# CH32V467VET-USB.net
KiCad netlist of a schematic drawn in Altium Designer
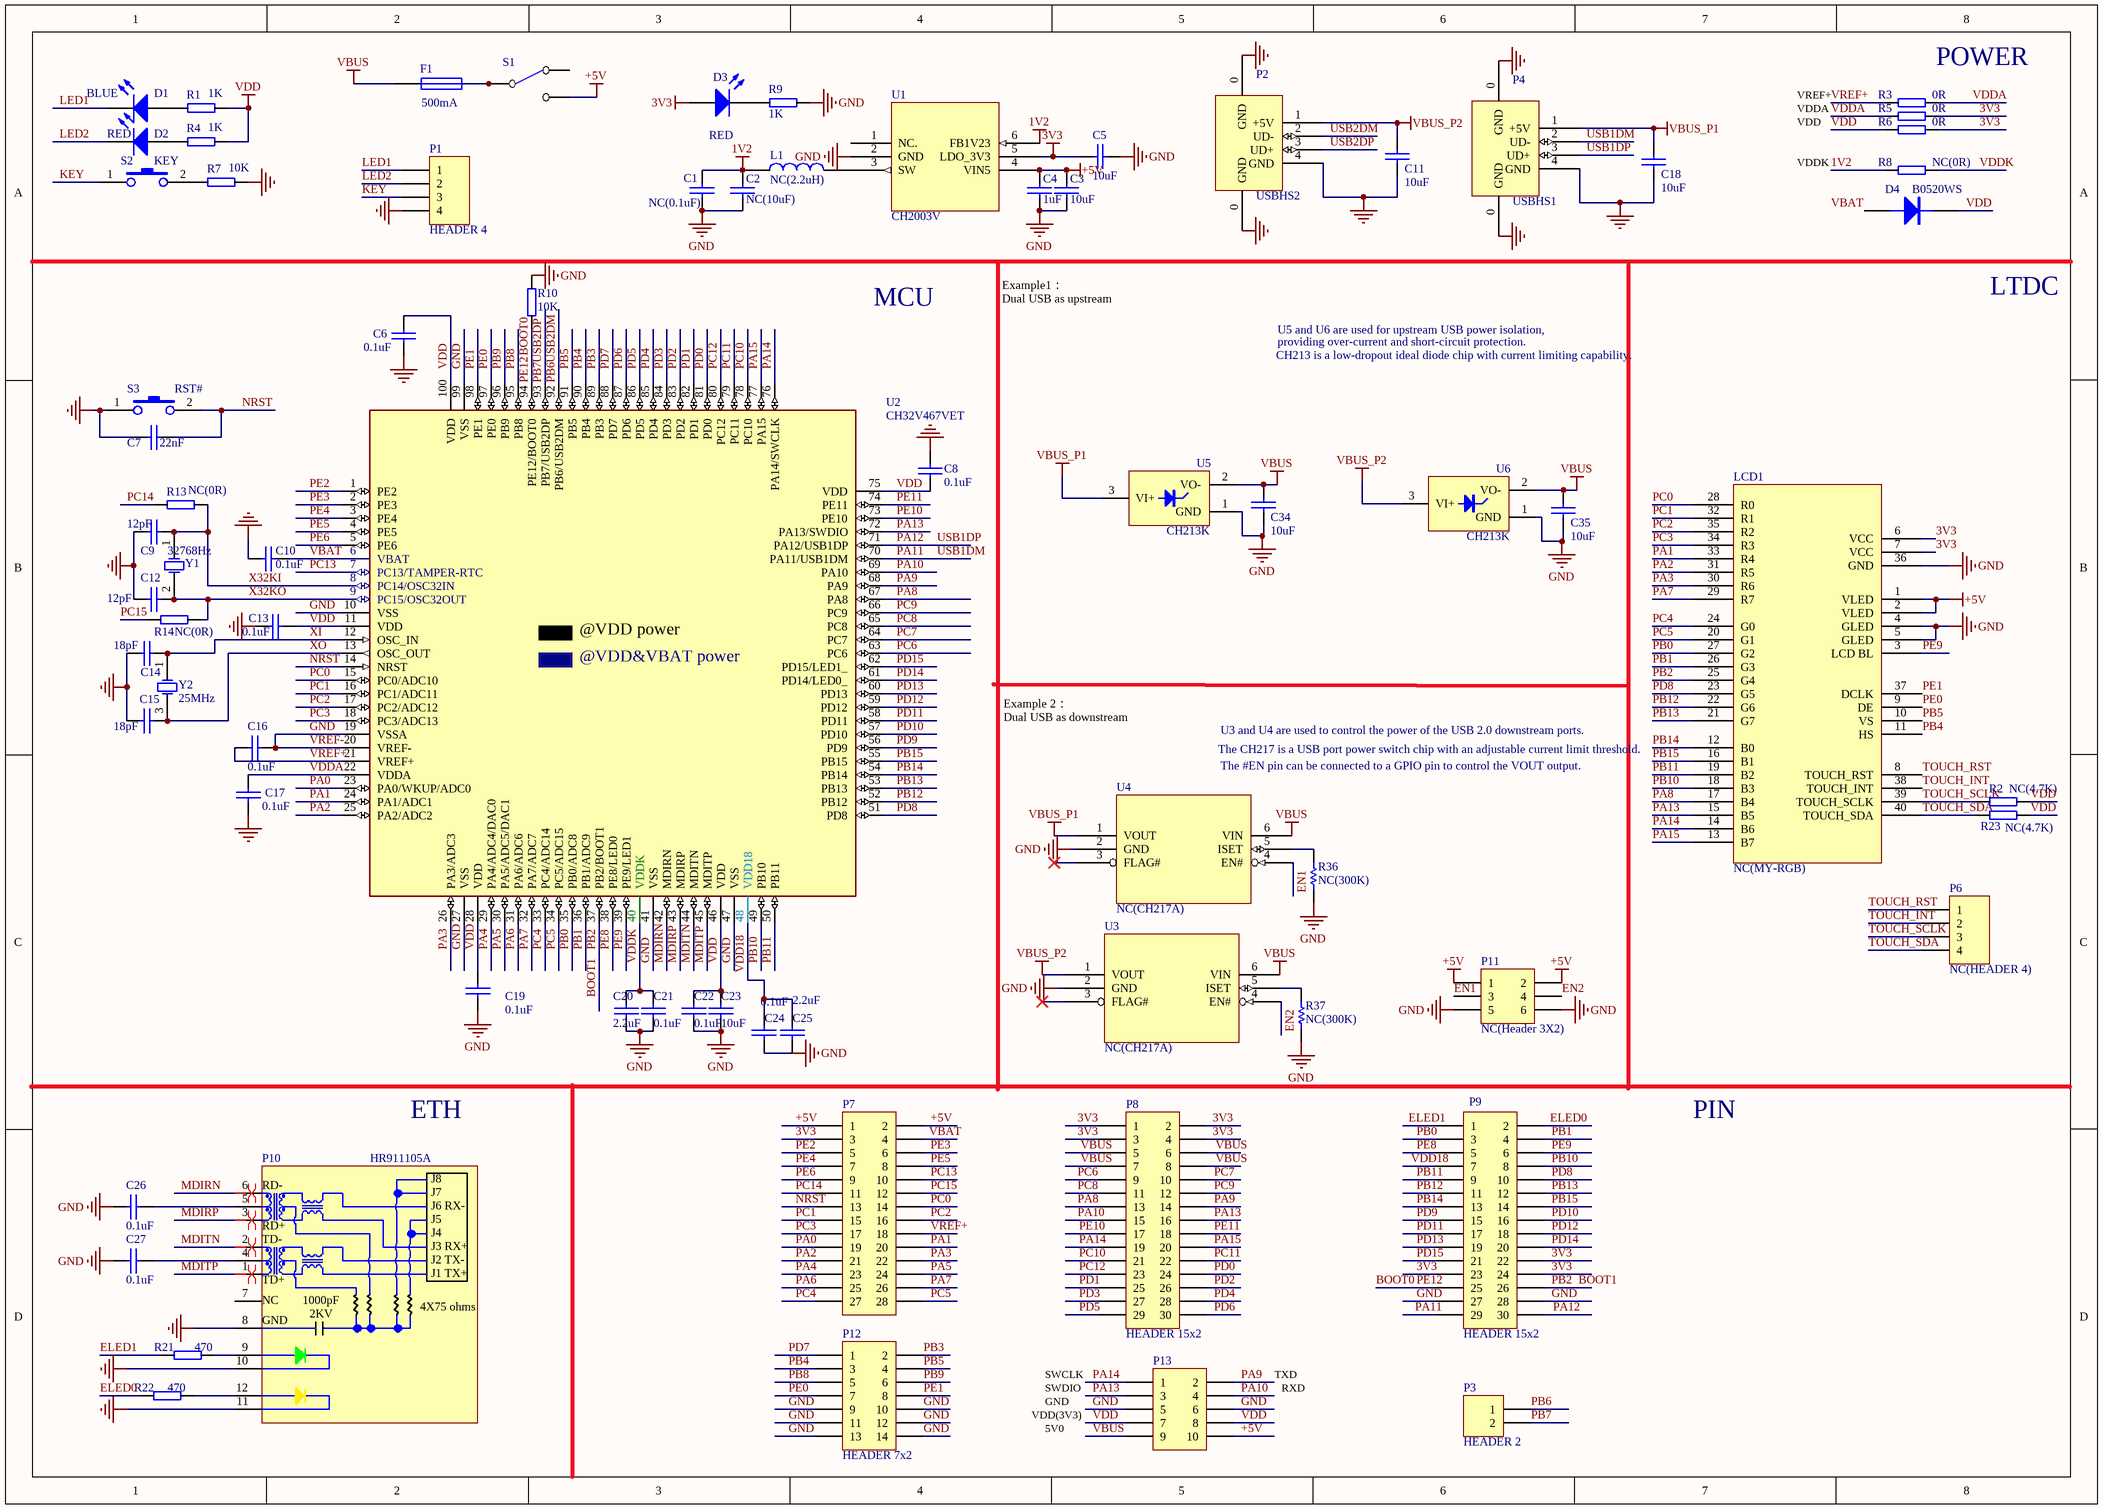
[diagram p0: CH32V467VET-USB.SchDoc]

(export (version "E")
  (design (tool "Eeschema 10.0.6"))
  (components
    (comp (ref "C1")
      (value "NC(0.1uF)")
      (footprint "0402_C")
      (description "Capacitor")
      (libsource (lib "") (part "CAP_2"))
    )
    (comp (ref "C2")
      (value "NC(10uF)")
      (footprint "0603_C")
      (description "Capacitor")
      (libsource (lib "*") (part "CAP"))
    )
    (comp (ref "C3")
      (value "10uF")
      (footprint "0603_C")
      (description "Capacitor")
      (libsource (lib "*") (part "CAP"))
    )
    (comp (ref "C4")
      (value "1uF")
      (footprint "0402_C")
      (description "Capacitor")
      (libsource (lib "") (part "CAP_2"))
    )
    (comp (ref "C5")
      (value "10uF")
      (footprint "0603_C")
      (description "Capacitor")
      (libsource (lib "*") (part "CAP"))
    )
    (comp (ref "C6")
      (value "0.1uF")
      (footprint "0402_C")
      (description "Capacitor")
      (libsource (lib "*") (part "CAP"))
    )
    (comp (ref "C7")
      (value "22nF")
      (footprint "0402_C")
      (description "Capacitor")
      (libsource (lib "") (part "CAP_1"))
    )
    (comp (ref "C8")
      (value "0.1uF")
      (footprint "0402_C")
      (description "Capacitor")
      (libsource (lib "*") (part "CAP"))
    )
    (comp (ref "C9")
      (value "12pF")
      (footprint "0402_C")
      (description "Capacitor")
      (libsource (lib "*") (part "CAP"))
    )
    (comp (ref "C10")
      (value "0.1uF")
      (footprint "0402_C")
      (description "Capacitor")
      (libsource (lib "*") (part "CAP"))
    )
    (comp (ref "C11")
      (value "10uF")
      (footprint "0603_C")
      (description "Capacitor")
      (libsource (lib "") (part "CAP_1"))
    )
    (comp (ref "C12")
      (value "12pF")
      (footprint "0402_C")
      (description "Capacitor")
      (libsource (lib "*") (part "CAP"))
    )
    (comp (ref "C13")
      (value "0.1uF")
      (footprint "0402_C")
      (description "Capacitor")
      (libsource (lib "*") (part "CAP"))
    )
    (comp (ref "C14")
      (value "18pF")
      (footprint "0402_C")
      (description "Capacitor")
      (libsource (lib "*") (part "CAP"))
    )
    (comp (ref "C15")
      (value "18pF")
      (footprint "0402_C")
      (description "Capacitor")
      (libsource (lib "*") (part "CAP"))
    )
    (comp (ref "C16")
      (value "0.1uF")
      (footprint "0402_C")
      (description "Capacitor")
      (libsource (lib "*") (part "CAP"))
    )
    (comp (ref "C17")
      (value "0.1uF")
      (footprint "0402_C")
      (description "Capacitor")
      (libsource (lib "*") (part "CAP"))
    )
    (comp (ref "C18")
      (value "10uF")
      (footprint "0603_C")
      (description "Capacitor")
      (libsource (lib "") (part "CAP_1"))
    )
    (comp (ref "C19")
      (value "0.1uF")
      (footprint "0402_C")
      (description "Capacitor")
      (libsource (lib "*") (part "CAP"))
    )
    (comp (ref "C20")
      (value "2.2uF")
      (footprint "0402_C")
      (description "Capacitor")
      (libsource (lib "*") (part "CAP"))
    )
    (comp (ref "C21")
      (value "0.1uF")
      (footprint "0402_C")
      (description "Capacitor")
      (libsource (lib "*") (part "CAP"))
    )
    (comp (ref "C22")
      (value "0.1uF")
      (footprint "0402_C")
      (description "Capacitor")
      (libsource (lib "*") (part "CAP"))
    )
    (comp (ref "C23")
      (value "10uF")
      (footprint "0402_C")
      (description "Capacitor")
      (libsource (lib "*") (part "CAP"))
    )
    (comp (ref "C24")
      (value "0.1uF")
      (footprint "0402_C")
      (description "Capacitor")
      (libsource (lib "*") (part "CAP"))
    )
    (comp (ref "C25")
      (value "2.2uF")
      (footprint "0402_C")
      (description "Capacitor")
      (libsource (lib "*") (part "CAP"))
    )
    (comp (ref "C26")
      (value "0.1uF")
      (footprint "0402_C")
      (description "Capacitor")
      (libsource (lib "wch_sch_others") (part "CAP"))
    )
    (comp (ref "C27")
      (value "0.1uF")
      (footprint "0402_C")
      (description "Capacitor")
      (libsource (lib "wch_sch_others") (part "CAP"))
    )
    (comp (ref "C34")
      (value "10uF")
      (footprint "0603_C")
      (description "Capacitor")
      (libsource (lib "") (part "CAP_1"))
    )
    (comp (ref "C35")
      (value "10uF")
      (footprint "0603_C")
      (description "Capacitor")
      (libsource (lib "") (part "CAP_1"))
    )
    (comp (ref "D1")
      (value "BLUE")
      (footprint "0603+")
      (description "Typical INFRARED GaAs LED")
      (fields (field (name "PUBLISHER") "Altium Limited"))
      (libsource (lib "*") (part "LED0"))
    )
    (comp (ref "D2")
      (value "RED")
      (footprint "0603+")
      (description "Typical INFRARED GaAs LED")
      (fields (field (name "PUBLISHER") "Altium Limited"))
      (libsource (lib "*") (part "LED0"))
    )
    (comp (ref "D3")
      (value "RED")
      (footprint "0603+")
      (description "Typical INFRARED GaAs LED")
      (fields (field (name "PUBLISHER") "Altium Limited"))
      (libsource (lib "*") (part "LED0"))
    )
    (comp (ref "D4")
      (value "B0520WS")
      (footprint "SOD-323")
      (description "Diode")
      (libsource (lib "*") (part "DIODE"))
    )
    (comp (ref "F1")
      (value "500mA")
      (footprint "0603")
      (description "Fuse")
      (libsource (lib "wch_sch_others") (part "FUSE1"))
    )
    (comp (ref "L1") (value "NC(2.2uH)") (footprint "CD32") (libsource (lib "*") (part "INDUCTOR")))
    (comp (ref "LCD1")
      (value "NC(MY-RGB)")
      (footprint "FPC40P-0.5-FK750M3")
      (libsource (lib "MY-显示") (part "MY-RGB"))
    )
    (comp (ref "P1")
      (value "HEADER 4")
      (footprint "SIP4-2.54mm")
      (description "Header, 4-Pin")
      (libsource (lib "wch_sch_others") (part "HEADER 4"))
    )
    (comp (ref "P2")
      (value "USBHS2")
      (footprint "USBAF")
      (description "USB Port")
      (libsource (lib "*") (part "USB"))
    )
    (comp (ref "P3")
      (value "HEADER 2")
      (footprint "MYPCB:SIP2-2.54mm")
      (description "Header, 2-Pin")
      (libsource (lib "wch_sch_others") (part "HEADER 2"))
    )
    (comp (ref "P4")
      (value "USBHS1")
      (footprint "USBAF")
      (description "USB Port")
      (libsource (lib "*") (part "USB"))
    )
    (comp (ref "P6")
      (value "NC(HEADER 4)")
      (footprint "SIP4-2.54mm")
      (description "Header, 4-Pin")
      (libsource (lib "wch_sch_others") (part "HEADER 4"))
    )
    (comp (ref "P7")
      (value "HEADER 14x2")
      (footprint "MYPCB:IDC28-2.54MM")
      (description "Header, 14-Pin, Dual row")
      (libsource (lib "wch_sch_others") (part "HEADER 14x2"))
    )
    (comp (ref "P8")
      (value "HEADER 15x2")
      (footprint "MYPCB:IDC30-2.54MM")
      (description "Header, 15-Pin, Dual row")
      (libsource (lib "wch_sch_others") (part "HEADER 15x2"))
    )
    (comp (ref "P9")
      (value "HEADER 15x2")
      (footprint "MYPCB:IDC30-2.54MM")
      (description "Header, 15-Pin, Dual row")
      (libsource (lib "wch_sch_others") (part "HEADER 15x2"))
    )
    (comp (ref "P10") (value "HR911105A") (footprint "HR911105A") (libsource (lib "*") (part "HR911105A")))
    (comp (ref "P11")
      (value "NC(Header 3X2)")
      (footprint "HDR2X3")
      (description "Header, 3-Pin, Dual row")
      (fields (field (name "PUBLISHER") "Altium Limited"))
      (libsource (lib "Miscellaneous Connectors") (part "Header 3X2"))
    )
    (comp (ref "P12")
      (value "HEADER 7x2")
      (footprint "MYPCB:IDC14-2.54mm")
      (description "Header, 7-Pin, Dual row")
      (libsource (lib "wch_sch_others") (part "HEADER 7x2"))
    )
    (comp (ref "P13")
      (value "LINK")
      (footprint "IDC10-2.54mm")
      (description "Header, 5-Pin, Dual row, Right Angle")
      (fields (field (name "PUBLISHER") "Altium Limited"))
      (libsource (lib "Miscellaneous Connectors") (part "Header 5X2H"))
    )
    (comp (ref "R1") (value "1K") (footprint "0402") (libsource (lib "wch_sch_others") (part "RES")))
    (comp (ref "R2") (value "NC(4.7K)") (footprint "0402") (libsource (lib "wch_sch_others") (part "RES")))
    (comp (ref "R3") (value "0R") (footprint "0402") (libsource (lib "*") (part "R")))
    (comp (ref "R4") (value "1K") (footprint "0402") (libsource (lib "wch_sch_others") (part "RES")))
    (comp (ref "R5") (value "0R") (footprint "0402") (libsource (lib "*") (part "R")))
    (comp (ref "R6") (value "0R") (footprint "0402") (libsource (lib "*") (part "R")))
    (comp (ref "R7") (value "10K") (footprint "0402") (libsource (lib "wch_sch_others") (part "RES")))
    (comp (ref "R8") (value "NC(0R)") (footprint "0402") (libsource (lib "*") (part "R")))
    (comp (ref "R9") (value "1K") (footprint "0402") (libsource (lib "wch_sch_others") (part "RES")))
    (comp (ref "R10") (value "10K") (footprint "0402") (libsource (lib "wch_sch_others") (part "RES")))
    (comp (ref "R13") (value "NC(0R)") (footprint "0402") (libsource (lib "wch_sch_others") (part "RES")))
    (comp (ref "R14") (value "NC(0R)") (footprint "0402") (libsource (lib "wch_sch_others") (part "RES")))
    (comp (ref "R21") (value "470") (footprint "0402") (libsource (lib "wch_sch_others") (part "RES")))
    (comp (ref "R22") (value "470") (footprint "0402") (libsource (lib "wch_sch_others") (part "RES")))
    (comp (ref "R23") (value "NC(4.7K)") (footprint "0402") (libsource (lib "wch_sch_others") (part "RES")))
    (comp (ref "R36")
      (value "NC(300K)")
      (footprint "0603")
      (description "Resistor")
      (fields (field (name "PUBLISHER") "Altium Limited"))
      (libsource (lib "MYLIB") (part "0603-1"))
    )
    (comp (ref "R37")
      (value "NC(300K)")
      (footprint "0603")
      (description "Resistor")
      (fields (field (name "PUBLISHER") "Altium Limited"))
      (libsource (lib "MYLIB") (part "0603-1"))
    )
    (comp (ref "S1") (value "SW SPDT") (footprint "SW1") (libsource (lib "*") (part "SW SPDT")))
    (comp (ref "S2")
      (value "KEY")
      (footprint "SMD_6.1x3.65x2.5mm-KEY")
      (libsource (lib "wch_sch_others") (part "KEY1"))
    )
    (comp (ref "S3")
      (value "RST#")
      (footprint "SMD_6.1x3.65x2.5mm-KEY")
      (libsource (lib "wch_sch_others") (part "KEY1"))
    )
    (comp (ref "U1")
      (value "CH2003V")
      (footprint "SOT-23-6")
      (description "Step-Down DC-DC Converter, 5V input, 1.23V * 800mA output, with LDO 3.3V * 200mA")
      (libsource (lib "CHXXX") (part "CH2003V"))
    )
    (comp (ref "U2")
      (value "CH32V467VET")
      (footprint "LQFP100")
      (description "RISC-V FPU HD-MCU, 175MHz, USB_480M, 100M Ethernet & Phy, CAN, DVP, ADC, DAC, SRAM")
      (libsource (lib "CHXXX") (part "CH32V467VET"))
    )
    (comp (ref "U3")
      (value "NC(CH217A)")
      (footprint "SOT-23-6")
      (description "Current-Limited USB Power Distribution Switch")
      (libsource (lib "CHXXX") (part "CH217K"))
    )
    (comp (ref "U4")
      (value "NC(CH217A)")
      (footprint "SOT-23-6")
      (description "Current-Limited USB Power Distribution Switch")
      (libsource (lib "CHXXX") (part "CH217K"))
    )
    (comp (ref "U5")
      (value "CH213K")
      (footprint "SOT-23-3")
      (description "Ideal Diode 5V*1A")
      (libsource (lib "*") (part "CH213K"))
    )
    (comp (ref "U6")
      (value "CH213K")
      (footprint "SOT-23-3")
      (description "Ideal Diode 5V*1A")
      (libsource (lib "*") (part "CH213K"))
    )
    (comp (ref "Y1")
      (value "32768Hz")
      (footprint "FC-135")
      (description "Crystal Oscillator")
      (fields (field (name "PUBLISHER") "Altium Limited"))
      (libsource (lib "") (part "XTAL_1"))
    )
    (comp (ref "Y2")
      (value "25MHz")
      (footprint "XT3225")
      (description "Crystal Oscillator")
      (fields (field (name "PUBLISHER") "Altium Limited"))
      (libsource (lib "*") (part "XTAL"))
    )
  )
  (nets
    (net (code "1") (name "+5V") (class "Default")
      (node (ref "C3") (pin "2") (pinfunction "2_2") (pintype "passive"))
      (node (ref "C4") (pin "2") (pinfunction "2_2") (pintype "passive"))
      (node (ref "LCD1") (pin "1") (pinfunction "VLED_1") (pintype "passive"))
      (node (ref "LCD1") (pin "2") (pinfunction "VLED_2") (pintype "passive"))
      (node (ref "P11") (pin "1") (pinfunction "1_1") (pintype "passive"))
      (node (ref "P11") (pin "2") (pinfunction "2_2") (pintype "passive"))
      (node (ref "P13") (pin "10") (pinfunction "10_10") (pintype "passive"))
      (node (ref "P7") (pin "1") (pinfunction "1_1") (pintype "passive"))
      (node (ref "P7") (pin "2") (pinfunction "2_2") (pintype "passive"))
      (node (ref "S1") (pin "2") (pinfunction "NC_2") (pintype "passive"))
      (node (ref "U1") (pin "4") (pinfunction "VIN5_4") (pintype "power_in"))
    )
    (net (code "3") (name "/BOOT0") (class "Default")
      (node (ref "P9") (pin "25") (pinfunction "25_25") (pintype "passive"))
      (node (ref "R10") (pin "2") (pintype "passive"))
      (node (ref "U2") (pin "94") (pinfunction "PE12/BOOT0_94") (pintype "bidirectional"))
    )
    (net (code "4") (name "/BOOT1") (class "Default")
      (node (ref "LCD1") (pin "25") (pinfunction "G4_25") (pintype "passive"))
      (node (ref "P9") (pin "26") (pinfunction "26_26") (pintype "passive"))
      (node (ref "U2") (pin "37") (pinfunction "PB2/BOOT1_37") (pintype "bidirectional"))
    )
    (net (code "5") (name "/ELED0") (class "Default")
      (node (ref "P9") (pin "2") (pinfunction "2_2") (pintype "passive"))
      (node (ref "R22") (pin "1") (pintype "passive"))
    )
    (net (code "6") (name "/ELED1") (class "Default")
      (node (ref "P9") (pin "1") (pinfunction "1_1") (pintype "passive"))
      (node (ref "R21") (pin "1") (pintype "passive"))
    )
    (net (code "7") (name "/EN1") (class "Default")
      (node (ref "P11") (pin "3") (pinfunction "3_3") (pintype "passive"))
      (node (ref "U4") (pin "4") (pinfunction "EN#_4") (pintype "input"))
    )
    (net (code "8") (name "/EN2") (class "Default")
      (node (ref "P11") (pin "4") (pinfunction "4_4") (pintype "passive"))
      (node (ref "U3") (pin "4") (pinfunction "EN#_4") (pintype "input"))
    )
    (net (code "9") (name "/KEY") (class "Default")
      (node (ref "P1") (pin "3") (pinfunction "3_3") (pintype "passive"))
      (node (ref "S2") (pin "1") (pinfunction "1_1") (pintype "passive"))
    )
    (net (code "10") (name "/LED1") (class "Default")
      (node (ref "D1") (pin "2") (pinfunction "K_2") (pintype "passive"))
      (node (ref "P1") (pin "1") (pinfunction "1_1") (pintype "passive"))
    )
    (net (code "11") (name "/LED2") (class "Default")
      (node (ref "D2") (pin "2") (pinfunction "K_2") (pintype "passive"))
      (node (ref "P1") (pin "2") (pinfunction "2_2") (pintype "passive"))
    )
    (net (code "12") (name "/MDIRN") (class "Default")
      (node (ref "P10") (pin "6") (pintype "passive"))
      (node (ref "U2") (pin "42") (pinfunction "MDIRN_42") (pintype "bidirectional"))
    )
    (net (code "13") (name "/MDIRP") (class "Default")
      (node (ref "P10") (pin "3") (pintype "passive"))
      (node (ref "U2") (pin "43") (pinfunction "MDIRP_43") (pintype "bidirectional"))
    )
    (net (code "14") (name "/MDITN") (class "Default")
      (node (ref "P10") (pin "2") (pintype "passive"))
      (node (ref "U2") (pin "44") (pinfunction "MDITN_44") (pintype "bidirectional"))
    )
    (net (code "15") (name "/MDITP") (class "Default")
      (node (ref "P10") (pin "1") (pintype "passive"))
      (node (ref "U2") (pin "45") (pinfunction "MDITP_45") (pintype "bidirectional"))
    )
    (net (code "16") (name "/NRST") (class "Default")
      (node (ref "C7") (pin "2") (pinfunction "2_2") (pintype "passive"))
      (node (ref "P7") (pin "13") (pinfunction "13_13") (pintype "passive"))
      (node (ref "S3") (pin "2") (pinfunction "2_2") (pintype "passive"))
      (node (ref "U2") (pin "14") (pinfunction "NRST_14") (pintype "input"))
    )
    (net (code "17") (name "/PA0") (class "Default")
      (node (ref "P7") (pin "19") (pinfunction "19_19") (pintype "passive"))
      (node (ref "U2") (pin "23") (pinfunction "PA0/WKUP/ADC0_23") (pintype "bidirectional"))
    )
    (net (code "18") (name "/PA1") (class "Default")
      (node (ref "LCD1") (pin "33") (pinfunction "R4_33") (pintype "passive"))
      (node (ref "P7") (pin "20") (pinfunction "20_20") (pintype "passive"))
      (node (ref "U2") (pin "24") (pinfunction "PA1/ADC1_24") (pintype "bidirectional"))
    )
    (net (code "19") (name "/PA2") (class "Default")
      (node (ref "LCD1") (pin "31") (pinfunction "R5_31") (pintype "passive"))
      (node (ref "P7") (pin "21") (pinfunction "21_21") (pintype "passive"))
      (node (ref "U2") (pin "25") (pinfunction "PA2/ADC2_25") (pintype "bidirectional"))
    )
    (net (code "20") (name "/PA3") (class "Default")
      (node (ref "LCD1") (pin "30") (pinfunction "R6_30") (pintype "passive"))
      (node (ref "P7") (pin "22") (pinfunction "22_22") (pintype "passive"))
      (node (ref "U2") (pin "26") (pinfunction "PA3/ADC3_26") (pintype "bidirectional"))
    )
    (net (code "21") (name "/PA4") (class "Default")
      (node (ref "P7") (pin "23") (pinfunction "23_23") (pintype "passive"))
      (node (ref "U2") (pin "29") (pinfunction "PA4/ADC4/DAC0_29") (pintype "bidirectional"))
    )
    (net (code "22") (name "/PA5") (class "Default")
      (node (ref "P7") (pin "24") (pinfunction "24_24") (pintype "passive"))
      (node (ref "U2") (pin "30") (pinfunction "PA5/ADC5/DAC1_30") (pintype "bidirectional"))
    )
    (net (code "23") (name "/PA6") (class "Default")
      (node (ref "P7") (pin "25") (pinfunction "25_25") (pintype "passive"))
      (node (ref "U2") (pin "31") (pinfunction "PA6/ADC6_31") (pintype "bidirectional"))
    )
    (net (code "24") (name "/PA7") (class "Default")
      (node (ref "LCD1") (pin "29") (pinfunction "R7_29") (pintype "passive"))
      (node (ref "P7") (pin "26") (pinfunction "26_26") (pintype "passive"))
      (node (ref "U2") (pin "32") (pinfunction "PA7/ADC7_32") (pintype "bidirectional"))
    )
    (net (code "25") (name "/PA8") (class "Default")
      (node (ref "LCD1") (pin "17") (pinfunction "B4_17") (pintype "passive"))
      (node (ref "P8") (pin "13") (pinfunction "13_13") (pintype "passive"))
      (node (ref "U2") (pin "67") (pinfunction "PA8_67") (pintype "bidirectional"))
    )
    (net (code "26") (name "/PA9") (class "Default")
      (node (ref "P13") (pin "2") (pinfunction "2_2") (pintype "passive"))
      (node (ref "P8") (pin "14") (pinfunction "14_14") (pintype "passive"))
      (node (ref "U2") (pin "68") (pinfunction "PA9_68") (pintype "bidirectional"))
    )
    (net (code "27") (name "/PA10") (class "Default")
      (node (ref "P13") (pin "4") (pinfunction "4_4") (pintype "passive"))
      (node (ref "P8") (pin "15") (pinfunction "15_15") (pintype "passive"))
      (node (ref "U2") (pin "69") (pinfunction "PA10_69") (pintype "bidirectional"))
    )
    (net (code "28") (name "/PA11") (class "Default")
      (node (ref "P4") (pin "2") (pinfunction "UD-_2") (pintype "bidirectional"))
      (node (ref "P9") (pin "29") (pinfunction "29_29") (pintype "passive"))
      (node (ref "U2") (pin "70") (pinfunction "PA11/USB1DM_70") (pintype "bidirectional"))
    )
    (net (code "29") (name "/PA12") (class "Default")
      (node (ref "P4") (pin "3") (pinfunction "UD+_3") (pintype "bidirectional"))
      (node (ref "P9") (pin "30") (pinfunction "30_30") (pintype "passive"))
      (node (ref "U2") (pin "71") (pinfunction "PA12/USB1DP_71") (pintype "bidirectional"))
    )
    (net (code "30") (name "/PA13") (class "Default")
      (node (ref "LCD1") (pin "15") (pinfunction "B5_15") (pintype "passive"))
      (node (ref "P13") (pin "3") (pinfunction "3_3") (pintype "passive"))
      (node (ref "P8") (pin "16") (pinfunction "16_16") (pintype "passive"))
      (node (ref "U2") (pin "72") (pinfunction "PA13/SWDIO_72") (pintype "bidirectional"))
    )
    (net (code "31") (name "/PA14") (class "Default")
      (node (ref "LCD1") (pin "14") (pinfunction "B6_14") (pintype "passive"))
      (node (ref "P13") (pin "1") (pinfunction "1_1") (pintype "passive"))
      (node (ref "P8") (pin "19") (pinfunction "19_19") (pintype "passive"))
      (node (ref "U2") (pin "76") (pinfunction "PA14/SWCLK_76") (pintype "bidirectional"))
    )
    (net (code "32") (name "/PA15") (class "Default")
      (node (ref "LCD1") (pin "13") (pinfunction "B7_13") (pintype "passive"))
      (node (ref "P8") (pin "20") (pinfunction "20_20") (pintype "passive"))
      (node (ref "U2") (pin "77") (pinfunction "PA15_77") (pintype "bidirectional"))
    )
    (net (code "33") (name "/PB0") (class "Default")
      (node (ref "LCD1") (pin "27") (pinfunction "G2_27") (pintype "passive"))
      (node (ref "P9") (pin "3") (pinfunction "3_3") (pintype "passive"))
      (node (ref "U2") (pin "35") (pinfunction "PB0/ADC8_35") (pintype "bidirectional"))
    )
    (net (code "34") (name "/PB1") (class "Default")
      (node (ref "LCD1") (pin "26") (pinfunction "G3_26") (pintype "passive"))
      (node (ref "P9") (pin "4") (pinfunction "4_4") (pintype "passive"))
      (node (ref "U2") (pin "36") (pinfunction "PB1/ADC9_36") (pintype "bidirectional"))
    )
    (net (code "35") (name "/PB3") (class "Default")
      (node (ref "P12") (pin "2") (pinfunction "2_2") (pintype "passive"))
      (node (ref "U2") (pin "89") (pinfunction "PB3_89") (pintype "bidirectional"))
    )
    (net (code "36") (name "/PB4") (class "Default")
      (node (ref "LCD1") (pin "11") (pinfunction "HS_11") (pintype "passive"))
      (node (ref "P12") (pin "3") (pinfunction "3_3") (pintype "passive"))
      (node (ref "U2") (pin "90") (pinfunction "PB4_90") (pintype "bidirectional"))
    )
    (net (code "37") (name "/PB5") (class "Default")
      (node (ref "LCD1") (pin "10") (pinfunction "VS_10") (pintype "passive"))
      (node (ref "P12") (pin "4") (pinfunction "4_4") (pintype "passive"))
      (node (ref "U2") (pin "91") (pinfunction "PB5_91") (pintype "bidirectional"))
    )
    (net (code "38") (name "/PB6") (class "Default")
      (node (ref "P2") (pin "2") (pinfunction "UD-_2") (pintype "bidirectional"))
      (node (ref "P3") (pin "1") (pinfunction "1_1") (pintype "passive"))
      (node (ref "U2") (pin "92") (pinfunction "PB6/USB2DM_92") (pintype "bidirectional"))
    )
    (net (code "39") (name "/PB7") (class "Default")
      (node (ref "P2") (pin "3") (pinfunction "UD+_3") (pintype "bidirectional"))
      (node (ref "P3") (pin "2") (pinfunction "2_2") (pintype "passive"))
      (node (ref "U2") (pin "93") (pinfunction "PB7/USB2DP_93") (pintype "bidirectional"))
    )
    (net (code "40") (name "/PB8") (class "Default")
      (node (ref "P12") (pin "5") (pinfunction "5_5") (pintype "passive"))
      (node (ref "U2") (pin "95") (pinfunction "PB8_95") (pintype "bidirectional"))
    )
    (net (code "41") (name "/PB9") (class "Default")
      (node (ref "P12") (pin "6") (pinfunction "6_6") (pintype "passive"))
      (node (ref "U2") (pin "96") (pinfunction "PB9_96") (pintype "bidirectional"))
    )
    (net (code "42") (name "/PB10") (class "Default")
      (node (ref "LCD1") (pin "18") (pinfunction "B3_18") (pintype "passive"))
      (node (ref "P9") (pin "8") (pinfunction "8_8") (pintype "passive"))
      (node (ref "U2") (pin "49") (pinfunction "PB10_49") (pintype "bidirectional"))
    )
    (net (code "43") (name "/PB11") (class "Default")
      (node (ref "LCD1") (pin "19") (pinfunction "B2_19") (pintype "passive"))
      (node (ref "P9") (pin "9") (pinfunction "9_9") (pintype "passive"))
      (node (ref "U2") (pin "50") (pinfunction "PB11_50") (pintype "bidirectional"))
    )
    (net (code "44") (name "/PB12") (class "Default")
      (node (ref "LCD1") (pin "22") (pinfunction "G6_22") (pintype "passive"))
      (node (ref "P9") (pin "11") (pinfunction "11_11") (pintype "passive"))
      (node (ref "U2") (pin "52") (pinfunction "PB12_52") (pintype "bidirectional"))
    )
    (net (code "45") (name "/PB13") (class "Default")
      (node (ref "LCD1") (pin "21") (pinfunction "G7_21") (pintype "passive"))
      (node (ref "P9") (pin "12") (pinfunction "12_12") (pintype "passive"))
      (node (ref "U2") (pin "53") (pinfunction "PB13_53") (pintype "bidirectional"))
    )
    (net (code "46") (name "/PB14") (class "Default")
      (node (ref "LCD1") (pin "12") (pinfunction "B0_12") (pintype "passive"))
      (node (ref "P9") (pin "13") (pinfunction "13_13") (pintype "passive"))
      (node (ref "U2") (pin "54") (pinfunction "PB14_54") (pintype "bidirectional"))
    )
    (net (code "47") (name "/PB15") (class "Default")
      (node (ref "LCD1") (pin "16") (pinfunction "B1_16") (pintype "passive"))
      (node (ref "P9") (pin "14") (pinfunction "14_14") (pintype "passive"))
      (node (ref "U2") (pin "55") (pinfunction "PB15_55") (pintype "bidirectional"))
    )
    (net (code "48") (name "/PC0") (class "Default")
      (node (ref "LCD1") (pin "28") (pinfunction "R0_28") (pintype "passive"))
      (node (ref "P7") (pin "14") (pinfunction "14_14") (pintype "passive"))
      (node (ref "U2") (pin "15") (pinfunction "PC0/ADC10_15") (pintype "bidirectional"))
    )
    (net (code "49") (name "/PC1") (class "Default")
      (node (ref "LCD1") (pin "32") (pinfunction "R1_32") (pintype "passive"))
      (node (ref "P7") (pin "15") (pinfunction "15_15") (pintype "passive"))
      (node (ref "U2") (pin "16") (pinfunction "PC1/ADC11_16") (pintype "bidirectional"))
    )
    (net (code "50") (name "/PC2") (class "Default")
      (node (ref "LCD1") (pin "35") (pinfunction "R2_35") (pintype "passive"))
      (node (ref "P7") (pin "16") (pinfunction "16_16") (pintype "passive"))
      (node (ref "U2") (pin "17") (pinfunction "PC2/ADC12_17") (pintype "bidirectional"))
    )
    (net (code "51") (name "/PC3") (class "Default")
      (node (ref "LCD1") (pin "34") (pinfunction "R3_34") (pintype "passive"))
      (node (ref "P7") (pin "17") (pinfunction "17_17") (pintype "passive"))
      (node (ref "U2") (pin "18") (pinfunction "PC3/ADC13_18") (pintype "bidirectional"))
    )
    (net (code "52") (name "/PC4") (class "Default")
      (node (ref "LCD1") (pin "24") (pinfunction "G0_24") (pintype "passive"))
      (node (ref "P7") (pin "27") (pinfunction "27_27") (pintype "passive"))
      (node (ref "U2") (pin "33") (pinfunction "PC4/ADC14_33") (pintype "bidirectional"))
    )
    (net (code "53") (name "/PC5") (class "Default")
      (node (ref "LCD1") (pin "20") (pinfunction "G1_20") (pintype "passive"))
      (node (ref "P7") (pin "28") (pinfunction "28_28") (pintype "passive"))
      (node (ref "U2") (pin "34") (pinfunction "PC5/ADC15_34") (pintype "bidirectional"))
    )
    (net (code "54") (name "/PC6") (class "Default")
      (node (ref "P8") (pin "9") (pinfunction "9_9") (pintype "passive"))
      (node (ref "U2") (pin "63") (pinfunction "PC6_63") (pintype "bidirectional"))
    )
    (net (code "55") (name "/PC7") (class "Default")
      (node (ref "P8") (pin "10") (pinfunction "10_10") (pintype "passive"))
      (node (ref "U2") (pin "64") (pinfunction "PC7_64") (pintype "bidirectional"))
    )
    (net (code "56") (name "/PC8") (class "Default")
      (node (ref "P8") (pin "11") (pinfunction "11_11") (pintype "passive"))
      (node (ref "U2") (pin "65") (pinfunction "PC8_65") (pintype "bidirectional"))
    )
    (net (code "57") (name "/PC9") (class "Default")
      (node (ref "P8") (pin "12") (pinfunction "12_12") (pintype "passive"))
      (node (ref "U2") (pin "66") (pinfunction "PC9_66") (pintype "bidirectional"))
    )
    (net (code "58") (name "/PC10") (class "Default")
      (node (ref "P8") (pin "21") (pinfunction "21_21") (pintype "passive"))
      (node (ref "U2") (pin "78") (pinfunction "PC10_78") (pintype "bidirectional"))
    )
    (net (code "59") (name "/PC11") (class "Default")
      (node (ref "P8") (pin "22") (pinfunction "22_22") (pintype "passive"))
      (node (ref "U2") (pin "79") (pinfunction "PC11_79") (pintype "bidirectional"))
    )
    (net (code "60") (name "/PC12") (class "Default")
      (node (ref "P8") (pin "23") (pinfunction "23_23") (pintype "passive"))
      (node (ref "U2") (pin "80") (pinfunction "PC12_80") (pintype "bidirectional"))
    )
    (net (code "61") (name "/PC13") (class "Default")
      (node (ref "P7") (pin "10") (pinfunction "10_10") (pintype "passive"))
      (node (ref "U2") (pin "7") (pinfunction "PC13/TAMPER-RTC_7") (pintype "bidirectional"))
    )
    (net (code "62") (name "/PC14") (class "Default")
      (node (ref "P7") (pin "11") (pinfunction "11_11") (pintype "passive"))
      (node (ref "R13") (pin "1") (pintype "passive"))
    )
    (net (code "63") (name "/PC15") (class "Default")
      (node (ref "P7") (pin "12") (pinfunction "12_12") (pintype "passive"))
      (node (ref "R14") (pin "1") (pintype "passive"))
    )
    (net (code "64") (name "/PD0") (class "Default")
      (node (ref "P8") (pin "24") (pinfunction "24_24") (pintype "passive"))
      (node (ref "U2") (pin "81") (pinfunction "PD0_81") (pintype "bidirectional"))
    )
    (net (code "65") (name "/PD1") (class "Default")
      (node (ref "P8") (pin "25") (pinfunction "25_25") (pintype "passive"))
      (node (ref "U2") (pin "82") (pinfunction "PD1_82") (pintype "bidirectional"))
    )
    (net (code "66") (name "/PD2") (class "Default")
      (node (ref "P8") (pin "26") (pinfunction "26_26") (pintype "passive"))
      (node (ref "U2") (pin "83") (pinfunction "PD2_83") (pintype "bidirectional"))
    )
    (net (code "67") (name "/PD3") (class "Default")
      (node (ref "P8") (pin "27") (pinfunction "27_27") (pintype "passive"))
      (node (ref "U2") (pin "84") (pinfunction "PD3_84") (pintype "bidirectional"))
    )
    (net (code "68") (name "/PD4") (class "Default")
      (node (ref "P8") (pin "28") (pinfunction "28_28") (pintype "passive"))
      (node (ref "U2") (pin "85") (pinfunction "PD4_85") (pintype "bidirectional"))
    )
    (net (code "69") (name "/PD5") (class "Default")
      (node (ref "P8") (pin "29") (pinfunction "29_29") (pintype "passive"))
      (node (ref "U2") (pin "86") (pinfunction "PD5_86") (pintype "bidirectional"))
    )
    (net (code "70") (name "/PD6") (class "Default")
      (node (ref "P8") (pin "30") (pinfunction "30_30") (pintype "passive"))
      (node (ref "U2") (pin "87") (pinfunction "PD6_87") (pintype "bidirectional"))
    )
    (net (code "71") (name "/PD7") (class "Default")
      (node (ref "P12") (pin "1") (pinfunction "1_1") (pintype "passive"))
      (node (ref "U2") (pin "88") (pinfunction "PD7_88") (pintype "bidirectional"))
    )
    (net (code "72") (name "/PD8") (class "Default")
      (node (ref "LCD1") (pin "23") (pinfunction "G5_23") (pintype "passive"))
      (node (ref "P9") (pin "10") (pinfunction "10_10") (pintype "passive"))
      (node (ref "U2") (pin "51") (pinfunction "PD8_51") (pintype "bidirectional"))
    )
    (net (code "73") (name "/PD9") (class "Default")
      (node (ref "P9") (pin "15") (pinfunction "15_15") (pintype "passive"))
      (node (ref "U2") (pin "56") (pinfunction "PD9_56") (pintype "bidirectional"))
    )
    (net (code "74") (name "/PD10") (class "Default")
      (node (ref "P9") (pin "16") (pinfunction "16_16") (pintype "passive"))
      (node (ref "U2") (pin "57") (pinfunction "PD10_57") (pintype "bidirectional"))
    )
    (net (code "75") (name "/PD11") (class "Default")
      (node (ref "P9") (pin "17") (pinfunction "17_17") (pintype "passive"))
      (node (ref "U2") (pin "58") (pinfunction "PD11_58") (pintype "bidirectional"))
    )
    (net (code "76") (name "/PD12") (class "Default")
      (node (ref "P9") (pin "18") (pinfunction "18_18") (pintype "passive"))
      (node (ref "U2") (pin "59") (pinfunction "PD12_59") (pintype "bidirectional"))
    )
    (net (code "77") (name "/PD13") (class "Default")
      (node (ref "P9") (pin "19") (pinfunction "19_19") (pintype "passive"))
      (node (ref "U2") (pin "60") (pinfunction "PD13_60") (pintype "bidirectional"))
    )
    (net (code "78") (name "/PD14") (class "Default")
      (node (ref "P9") (pin "20") (pinfunction "20_20") (pintype "passive"))
      (node (ref "U2") (pin "61") (pinfunction "PD14/LED0__61") (pintype "bidirectional"))
    )
    (net (code "79") (name "/PD15") (class "Default")
      (node (ref "P9") (pin "21") (pinfunction "21_21") (pintype "passive"))
      (node (ref "U2") (pin "62") (pinfunction "PD15/LED1__62") (pintype "bidirectional"))
    )
    (net (code "80") (name "/PE0") (class "Default")
      (node (ref "LCD1") (pin "9") (pinfunction "DE_9") (pintype "passive"))
      (node (ref "P12") (pin "7") (pinfunction "7_7") (pintype "passive"))
      (node (ref "U2") (pin "97") (pinfunction "PE0_97") (pintype "bidirectional"))
    )
    (net (code "81") (name "/PE1") (class "Default")
      (node (ref "LCD1") (pin "37") (pinfunction "DCLK_37") (pintype "passive"))
      (node (ref "P12") (pin "8") (pinfunction "8_8") (pintype "passive"))
      (node (ref "U2") (pin "98") (pinfunction "PE1_98") (pintype "bidirectional"))
    )
    (net (code "82") (name "/PE2") (class "Default")
      (node (ref "P7") (pin "5") (pinfunction "5_5") (pintype "passive"))
      (node (ref "U2") (pin "1") (pinfunction "PE2_1") (pintype "bidirectional"))
    )
    (net (code "83") (name "/PE3") (class "Default")
      (node (ref "P7") (pin "6") (pinfunction "6_6") (pintype "passive"))
      (node (ref "U2") (pin "2") (pinfunction "PE3_2") (pintype "bidirectional"))
    )
    (net (code "84") (name "/PE4") (class "Default")
      (node (ref "P7") (pin "7") (pinfunction "7_7") (pintype "passive"))
      (node (ref "U2") (pin "3") (pinfunction "PE4_3") (pintype "bidirectional"))
    )
    (net (code "85") (name "/PE5") (class "Default")
      (node (ref "P7") (pin "8") (pinfunction "8_8") (pintype "passive"))
      (node (ref "U2") (pin "4") (pinfunction "PE5_4") (pintype "bidirectional"))
    )
    (net (code "86") (name "/PE6") (class "Default")
      (node (ref "P7") (pin "9") (pinfunction "9_9") (pintype "passive"))
      (node (ref "U2") (pin "5") (pinfunction "PE6_5") (pintype "bidirectional"))
    )
    (net (code "87") (name "/PE8") (class "Default")
      (node (ref "P9") (pin "5") (pinfunction "5_5") (pintype "passive"))
      (node (ref "U2") (pin "38") (pinfunction "PE8/LED0_38") (pintype "bidirectional"))
    )
    (net (code "88") (name "/PE9") (class "Default")
      (node (ref "LCD1") (pin "3") (pinfunction "LCD_BL_3") (pintype "passive"))
      (node (ref "P9") (pin "6") (pinfunction "6_6") (pintype "passive"))
      (node (ref "U2") (pin "39") (pinfunction "PE9/LED1_39") (pintype "bidirectional"))
    )
    (net (code "89") (name "/PE10") (class "Default")
      (node (ref "P8") (pin "17") (pinfunction "17_17") (pintype "passive"))
      (node (ref "U2") (pin "73") (pinfunction "PE10_73") (pintype "bidirectional"))
    )
    (net (code "90") (name "/PE11") (class "Default")
      (node (ref "P8") (pin "18") (pinfunction "18_18") (pintype "passive"))
      (node (ref "U2") (pin "74") (pinfunction "PE11_74") (pintype "bidirectional"))
    )
    (net (code "91") (name "/TOUCH_INT") (class "Default")
      (node (ref "LCD1") (pin "38") (pinfunction "TOUCH_INT_38") (pintype "passive"))
      (node (ref "P6") (pin "2") (pinfunction "2_2") (pintype "passive"))
    )
    (net (code "92") (name "/TOUCH_RST") (class "Default")
      (node (ref "LCD1") (pin "8") (pinfunction "TOUCH_RST_8") (pintype "passive"))
      (node (ref "P6") (pin "1") (pinfunction "1_1") (pintype "passive"))
    )
    (net (code "93") (name "/TOUCH_SCLK") (class "Default")
      (node (ref "LCD1") (pin "39") (pinfunction "TOUCH_SCLK_39") (pintype "passive"))
      (node (ref "P6") (pin "3") (pinfunction "3_3") (pintype "passive"))
      (node (ref "R2") (pin "2") (pintype "passive"))
    )
    (net (code "94") (name "/TOUCH_SDA") (class "Default")
      (node (ref "LCD1") (pin "40") (pinfunction "TOUCH_SDA_40") (pintype "passive"))
      (node (ref "P6") (pin "4") (pinfunction "4_4") (pintype "passive"))
      (node (ref "R23") (pin "2") (pintype "passive"))
    )
    (net (code "95") (name "/VBAT") (class "Default")
      (node (ref "C10") (pin "2") (pinfunction "2_2") (pintype "passive"))
      (node (ref "P7") (pin "4") (pinfunction "4_4") (pintype "passive"))
      (node (ref "U2") (pin "6") (pinfunction "VBAT_6") (pintype "power_in"))
    )
    (net (code "96") (name "/VDD18") (class "Default")
      (node (ref "C24") (pin "2") (pinfunction "2_2") (pintype "passive"))
      (node (ref "C25") (pin "2") (pinfunction "2_2") (pintype "passive"))
      (node (ref "P9") (pin "7") (pinfunction "7_7") (pintype "passive"))
      (node (ref "U2") (pin "48") (pinfunction "VDD18_48") (pintype "power_in"))
    )
    (net (code "97") (name "/VDDA") (class "Default")
      (node (ref "C17") (pin "1") (pinfunction "1_1") (pintype "passive"))
      (node (ref "R3") (pin "1") (pinfunction "1_1") (pintype "passive"))
      (node (ref "R5") (pin "2") (pinfunction "2_2") (pintype "passive"))
      (node (ref "U2") (pin "22") (pinfunction "VDDA_22") (pintype "power_in"))
    )
    (net (code "98") (name "/VDDK") (class "Default")
      (node (ref "C20") (pin "2") (pinfunction "2_2") (pintype "passive"))
      (node (ref "C21") (pin "2") (pinfunction "2_2") (pintype "passive"))
      (node (ref "R8") (pin "1") (pinfunction "1_1") (pintype "passive"))
      (node (ref "U2") (pin "40") (pinfunction "VDDK_40") (pintype "power_in"))
    )
    (net (code "99") (name "/VREF+") (class "Default")
      (node (ref "C16") (pin "1") (pinfunction "1_1") (pintype "passive"))
      (node (ref "P7") (pin "18") (pinfunction "18_18") (pintype "passive"))
      (node (ref "R3") (pin "2") (pinfunction "2_2") (pintype "passive"))
      (node (ref "U2") (pin "21") (pinfunction "VREF+_21") (pintype "power_in"))
    )
    (net (code "100") (name "/X32KI") (class "Default")
      (node (ref "C9") (pin "2") (pinfunction "2_2") (pintype "passive"))
      (node (ref "R13") (pin "2") (pintype "passive"))
      (node (ref "U2") (pin "8") (pinfunction "PC14/OSC32IN_8") (pintype "bidirectional"))
      (node (ref "Y1") (pin "1") (pinfunction "OSC1_1") (pintype "passive"))
    )
    (net (code "101") (name "/X32KO") (class "Default")
      (node (ref "C12") (pin "2") (pinfunction "2_2") (pintype "passive"))
      (node (ref "R14") (pin "2") (pintype "passive"))
      (node (ref "U2") (pin "9") (pinfunction "PC15/OSC32OUT_9") (pintype "bidirectional"))
      (node (ref "Y1") (pin "2") (pinfunction "OSC2_2") (pintype "passive"))
    )
    (net (code "102") (name "/XI") (class "Default")
      (node (ref "C14") (pin "2") (pinfunction "2_2") (pintype "passive"))
      (node (ref "U2") (pin "12") (pinfunction "OSC_IN_12") (pintype "input"))
      (node (ref "Y2") (pin "1") (pinfunction "OSC1_1") (pintype "passive"))
    )
    (net (code "103") (name "/XO") (class "Default")
      (node (ref "C15") (pin "2") (pinfunction "2_2") (pintype "passive"))
      (node (ref "U2") (pin "13") (pinfunction "OSC_OUT_13") (pintype "output"))
      (node (ref "Y2") (pin "3") (pinfunction "OSC2_3") (pintype "passive"))
    )
    (net (code "104") (name "1V2") (class "Default")
      (node (ref "C1") (pin "2") (pinfunction "2_2") (pintype "passive"))
      (node (ref "C2") (pin "2") (pinfunction "2_2") (pintype "passive"))
      (node (ref "L1") (pin "2") (pinfunction "2_2") (pintype "passive"))
      (node (ref "R8") (pin "2") (pinfunction "2_2") (pintype "passive"))
      (node (ref "U1") (pin "6") (pinfunction "FB1V23_6") (pintype "input"))
    )
    (net (code "105") (name "3V3") (class "Default")
      (node (ref "C5") (pin "2") (pinfunction "2_2") (pintype "passive"))
      (node (ref "D3") (pin "1") (pinfunction "A_1") (pintype "passive"))
      (node (ref "LCD1") (pin "6") (pinfunction "VCC_6") (pintype "passive"))
      (node (ref "LCD1") (pin "7") (pinfunction "VCC_7") (pintype "passive"))
      (node (ref "P7") (pin "3") (pinfunction "3_3") (pintype "passive"))
      (node (ref "P8") (pin "1") (pinfunction "1_1") (pintype "passive"))
      (node (ref "P8") (pin "2") (pinfunction "2_2") (pintype "passive"))
      (node (ref "P8") (pin "3") (pinfunction "3_3") (pintype "passive"))
      (node (ref "P8") (pin "4") (pinfunction "4_4") (pintype "passive"))
      (node (ref "P9") (pin "22") (pinfunction "22_22") (pintype "passive"))
      (node (ref "P9") (pin "23") (pinfunction "23_23") (pintype "passive"))
      (node (ref "P9") (pin "24") (pinfunction "24_24") (pintype "passive"))
      (node (ref "R5") (pin "1") (pinfunction "1_1") (pintype "passive"))
      (node (ref "R6") (pin "1") (pinfunction "1_1") (pintype "passive"))
      (node (ref "U1") (pin "5") (pinfunction "LDO_3V3_5") (pintype "power_in"))
    )
    (net (code "106") (name "GND") (class "Default")
      (node (ref "C1") (pin "1") (pinfunction "1_1") (pintype "passive"))
      (node (ref "C10") (pin "1") (pinfunction "1_1") (pintype "passive"))
      (node (ref "C11") (pin "2") (pinfunction "2_2") (pintype "passive"))
      (node (ref "C12") (pin "1") (pinfunction "1_1") (pintype "passive"))
      (node (ref "C13") (pin "2") (pinfunction "2_2") (pintype "passive"))
      (node (ref "C14") (pin "1") (pinfunction "1_1") (pintype "passive"))
      (node (ref "C15") (pin "1") (pinfunction "1_1") (pintype "passive"))
      (node (ref "C16") (pin "2") (pinfunction "2_2") (pintype "passive"))
      (node (ref "C17") (pin "2") (pinfunction "2_2") (pintype "passive"))
      (node (ref "C18") (pin "2") (pinfunction "2_2") (pintype "passive"))
      (node (ref "C19") (pin "1") (pinfunction "1_1") (pintype "passive"))
      (node (ref "C2") (pin "1") (pinfunction "1_1") (pintype "passive"))
      (node (ref "C20") (pin "1") (pinfunction "1_1") (pintype "passive"))
      (node (ref "C21") (pin "1") (pinfunction "1_1") (pintype "passive"))
      (node (ref "C22") (pin "1") (pinfunction "1_1") (pintype "passive"))
      (node (ref "C23") (pin "1") (pinfunction "1_1") (pintype "passive"))
      (node (ref "C25") (pin "1") (pinfunction "1_1") (pintype "passive"))
      (node (ref "C26") (pin "1") (pinfunction "1_1") (pintype "passive"))
      (node (ref "C27") (pin "1") (pinfunction "1_1") (pintype "passive"))
      (node (ref "C3") (pin "1") (pinfunction "1_1") (pintype "passive"))
      (node (ref "C34") (pin "2") (pinfunction "2_2") (pintype "passive"))
      (node (ref "C35") (pin "2") (pinfunction "2_2") (pintype "passive"))
      (node (ref "C4") (pin "1") (pinfunction "1_1") (pintype "passive"))
      (node (ref "C5") (pin "1") (pinfunction "1_1") (pintype "passive"))
      (node (ref "C6") (pin "1") (pinfunction "1_1") (pintype "passive"))
      (node (ref "C7") (pin "1") (pinfunction "1_1") (pintype "passive"))
      (node (ref "C8") (pin "2") (pinfunction "2_2") (pintype "passive"))
      (node (ref "C9") (pin "1") (pinfunction "1_1") (pintype "passive"))
      (node (ref "LCD1") (pin "36") (pinfunction "GND_36") (pintype "passive"))
      (node (ref "LCD1") (pin "4") (pinfunction "GLED_4") (pintype "passive"))
      (node (ref "LCD1") (pin "5") (pinfunction "GLED_5") (pintype "passive"))
      (node (ref "P1") (pin "4") (pinfunction "4_4") (pintype "passive"))
      (node (ref "P10") (pin "10") (pintype "passive"))
      (node (ref "P10") (pin "11") (pintype "passive"))
      (node (ref "P10") (pin "8") (pintype "passive"))
      (node (ref "P11") (pin "5") (pinfunction "5_5") (pintype "passive"))
      (node (ref "P11") (pin "6") (pinfunction "6_6") (pintype "passive"))
      (node (ref "P12") (pin "10") (pinfunction "10_10") (pintype "passive"))
      (node (ref "P12") (pin "11") (pinfunction "11_11") (pintype "passive"))
      (node (ref "P12") (pin "12") (pinfunction "12_12") (pintype "passive"))
      (node (ref "P12") (pin "13") (pinfunction "13_13") (pintype "passive"))
      (node (ref "P12") (pin "14") (pinfunction "14_14") (pintype "passive"))
      (node (ref "P12") (pin "9") (pinfunction "9_9") (pintype "passive"))
      (node (ref "P13") (pin "5") (pinfunction "5_5") (pintype "passive"))
      (node (ref "P13") (pin "6") (pinfunction "6_6") (pintype "passive"))
      (node (ref "P2") (pin "0") (pinfunction "GND_0") (pintype "power_in"))
      (node (ref "P2") (pin "4") (pinfunction "GND_4") (pintype "power_in"))
      (node (ref "P4") (pin "0") (pinfunction "GND_0") (pintype "power_in"))
      (node (ref "P4") (pin "4") (pinfunction "GND_4") (pintype "power_in"))
      (node (ref "P9") (pin "27") (pinfunction "27_27") (pintype "passive"))
      (node (ref "P9") (pin "28") (pinfunction "28_28") (pintype "passive"))
      (node (ref "R10") (pin "1") (pintype "passive"))
      (node (ref "R36") (pin "2") (pinfunction "2_2") (pintype "passive"))
      (node (ref "R37") (pin "2") (pinfunction "2_2") (pintype "passive"))
      (node (ref "R7") (pin "1") (pintype "passive"))
      (node (ref "R9") (pin "2") (pintype "passive"))
      (node (ref "S3") (pin "1") (pinfunction "1_1") (pintype "passive"))
      (node (ref "U1") (pin "2") (pinfunction "GND_2") (pintype "power_in"))
      (node (ref "U2") (pin "10") (pinfunction "VSS_10") (pintype "power_in"))
      (node (ref "U2") (pin "19") (pinfunction "VSSA_19") (pintype "power_in"))
      (node (ref "U2") (pin "20") (pinfunction "VREF-_20") (pintype "power_in"))
      (node (ref "U2") (pin "27") (pinfunction "VSS_27") (pintype "power_in"))
      (node (ref "U2") (pin "41") (pinfunction "VSS_41") (pintype "power_in"))
      (node (ref "U2") (pin "47") (pinfunction "VSS_47") (pintype "power_in"))
      (node (ref "U2") (pin "99") (pinfunction "VSS_99") (pintype "power_in"))
      (node (ref "U3") (pin "2") (pinfunction "GND_2") (pintype "power_in"))
      (node (ref "U4") (pin "2") (pinfunction "GND_2") (pintype "power_in"))
      (node (ref "U5") (pin "1") (pinfunction "GND_1") (pintype "power_in"))
      (node (ref "U6") (pin "1") (pinfunction "GND_1") (pintype "power_in"))
    )
    (net (code "107") (name "Net-(C26-Pad2)") (class "Default")
      (node (ref "C26") (pin "2") (pinfunction "2_2") (pintype "passive"))
      (node (ref "P10") (pin "5") (pintype "passive"))
    )
    (net (code "108") (name "Net-(C27-Pad2)") (class "Default")
      (node (ref "C27") (pin "2") (pinfunction "2_2") (pintype "passive"))
      (node (ref "P10") (pin "4") (pintype "passive"))
    )
    (net (code "109") (name "Net-(D1-A)") (class "Default")
      (node (ref "D1") (pin "1") (pinfunction "A_1") (pintype "passive"))
      (node (ref "R1") (pin "2") (pintype "passive"))
    )
    (net (code "110") (name "Net-(D2-A)") (class "Default")
      (node (ref "D2") (pin "1") (pinfunction "A_1") (pintype "passive"))
      (node (ref "R4") (pin "2") (pintype "passive"))
    )
    (net (code "111") (name "Net-(D3-K)") (class "Default")
      (node (ref "D3") (pin "2") (pinfunction "K_2") (pintype "passive"))
      (node (ref "R9") (pin "1") (pintype "passive"))
    )
    (net (code "112") (name "Net-(P10-Pad9)") (class "Default")
      (node (ref "P10") (pin "9") (pintype "passive"))
      (node (ref "R21") (pin "2") (pintype "passive"))
    )
    (net (code "113") (name "Net-(P10-Pad12)") (class "Default")
      (node (ref "P10") (pin "12") (pintype "passive"))
      (node (ref "R22") (pin "2") (pintype "passive"))
    )
    (net (code "114") (name "Net-(R7-Pad2)") (class "Default")
      (node (ref "R7") (pin "2") (pintype "passive"))
      (node (ref "S2") (pin "2") (pinfunction "2_2") (pintype "passive"))
    )
    (net (code "115") (name "Net-(S1-COMMON)") (class "Default")
      (node (ref "F1") (pin "2") (pinfunction "2_2") (pintype "passive"))
      (node (ref "S1") (pin "1") (pinfunction "COMMON_1") (pintype "passive"))
    )
    (net (code "116") (name "Net-(U1-SW)") (class "Default")
      (node (ref "L1") (pin "1") (pinfunction "1_1") (pintype "passive"))
      (node (ref "U1") (pin "3") (pinfunction "SW_3") (pintype "output"))
    )
    (net (code "117") (name "Net-(U3-ISET)") (class "Default")
      (node (ref "R37") (pin "1") (pinfunction "1_1") (pintype "passive"))
      (node (ref "U3") (pin "5") (pinfunction "ISET_5") (pintype "bidirectional"))
    )
    (net (code "118") (name "Net-(U4-ISET)") (class "Default")
      (node (ref "R36") (pin "1") (pinfunction "1_1") (pintype "passive"))
      (node (ref "U4") (pin "5") (pinfunction "ISET_5") (pintype "bidirectional"))
    )
    (net (code "119") (name "VBUS") (class "Default")
      (node (ref "C34") (pin "1") (pinfunction "1_1") (pintype "passive"))
      (node (ref "C35") (pin "1") (pinfunction "1_1") (pintype "passive"))
      (node (ref "F1") (pin "1") (pinfunction "1_1") (pintype "passive"))
      (node (ref "P13") (pin "9") (pinfunction "9_9") (pintype "passive"))
      (node (ref "P8") (pin "5") (pinfunction "5_5") (pintype "passive"))
      (node (ref "P8") (pin "6") (pinfunction "6_6") (pintype "passive"))
      (node (ref "P8") (pin "7") (pinfunction "7_7") (pintype "passive"))
      (node (ref "P8") (pin "8") (pinfunction "8_8") (pintype "passive"))
      (node (ref "U3") (pin "6") (pinfunction "VIN_6") (pintype "power_in"))
      (node (ref "U4") (pin "6") (pinfunction "VIN_6") (pintype "power_in"))
      (node (ref "U5") (pin "2") (pinfunction "VO-_2") (pintype "power_in"))
      (node (ref "U6") (pin "2") (pinfunction "VO-_2") (pintype "power_in"))
    )
    (net (code "120") (name "VBUS_P1") (class "Default")
      (node (ref "C18") (pin "1") (pinfunction "1_1") (pintype "passive"))
      (node (ref "P4") (pin "1") (pinfunction "+5V_1") (pintype "power_in"))
      (node (ref "U4") (pin "1") (pinfunction "VOUT_1") (pintype "power_in"))
      (node (ref "U5") (pin "3") (pinfunction "VI+_3") (pintype "power_in"))
    )
    (net (code "121") (name "VBUS_P2") (class "Default")
      (node (ref "C11") (pin "1") (pinfunction "1_1") (pintype "passive"))
      (node (ref "P2") (pin "1") (pinfunction "+5V_1") (pintype "power_in"))
      (node (ref "U3") (pin "1") (pinfunction "VOUT_1") (pintype "power_in"))
      (node (ref "U6") (pin "3") (pinfunction "VI+_3") (pintype "power_in"))
    )
    (net (code "122") (name "VDD") (class "Default")
      (node (ref "C13") (pin "1") (pinfunction "1_1") (pintype "passive"))
      (node (ref "C19") (pin "2") (pinfunction "2_2") (pintype "passive"))
      (node (ref "C22") (pin "2") (pinfunction "2_2") (pintype "passive"))
      (node (ref "C23") (pin "2") (pinfunction "2_2") (pintype "passive"))
      (node (ref "C6") (pin "2") (pinfunction "2_2") (pintype "passive"))
      (node (ref "C8") (pin "1") (pinfunction "1_1") (pintype "passive"))
      (node (ref "D4") (pin "2") (pinfunction "K_2") (pintype "passive"))
      (node (ref "P13") (pin "7") (pinfunction "7_7") (pintype "passive"))
      (node (ref "P13") (pin "8") (pinfunction "8_8") (pintype "passive"))
      (node (ref "R1") (pin "1") (pintype "passive"))
      (node (ref "R2") (pin "1") (pintype "passive"))
      (node (ref "R23") (pin "1") (pintype "passive"))
      (node (ref "R4") (pin "1") (pintype "passive"))
      (node (ref "R6") (pin "2") (pinfunction "2_2") (pintype "passive"))
      (node (ref "U2") (pin "100") (pinfunction "VDD_100") (pintype "power_in"))
      (node (ref "U2") (pin "11") (pinfunction "VDD_11") (pintype "power_in"))
      (node (ref "U2") (pin "28") (pinfunction "VDD_28") (pintype "power_in"))
      (node (ref "U2") (pin "46") (pinfunction "VDD_46") (pintype "power_in"))
      (node (ref "U2") (pin "75") (pinfunction "VDD_75") (pintype "power_in"))
    )
    (net (code "123") (name "unconnected-(C24-Pad1)") (class "Default")
      (node (ref "C24") (pin "1") (pinfunction "1_1") (pintype "passive"))
    )
    (net (code "124") (name "unconnected-(D4-A-Pad1)") (class "Default")
      (node (ref "D4") (pin "1") (pinfunction "A_1") (pintype "passive"))
    )
    (net (code "125") (name "unconnected-(P10-Pad7)") (class "Default")
      (node (ref "P10") (pin "7") (pintype "passive"))
    )
    (net (code "126") (name "unconnected-(S1-NO-Pad3)") (class "Default")
      (node (ref "S1") (pin "3") (pinfunction "NO_3") (pintype "passive"))
    )
    (net (code "127") (name "unconnected-(U1-NC.-Pad1)") (class "Default")
      (node (ref "U1") (pin "1") (pinfunction "NC._1") (pintype "passive"))
    )
    (net (code "128") (name "unconnected-(U3-FLAG#-Pad3)") (class "Default")
      (node (ref "U3") (pin "3") (pinfunction "FLAG#_3") (pintype "open_collector+no_connect"))
    )
    (net (code "129") (name "unconnected-(U4-FLAG#-Pad3)") (class "Default")
      (node (ref "U4") (pin "3") (pinfunction "FLAG#_3") (pintype "open_collector+no_connect"))
    )
  )
)
